# WQLT.net
KiCad netlist of a schematic drawn in Altium Designer
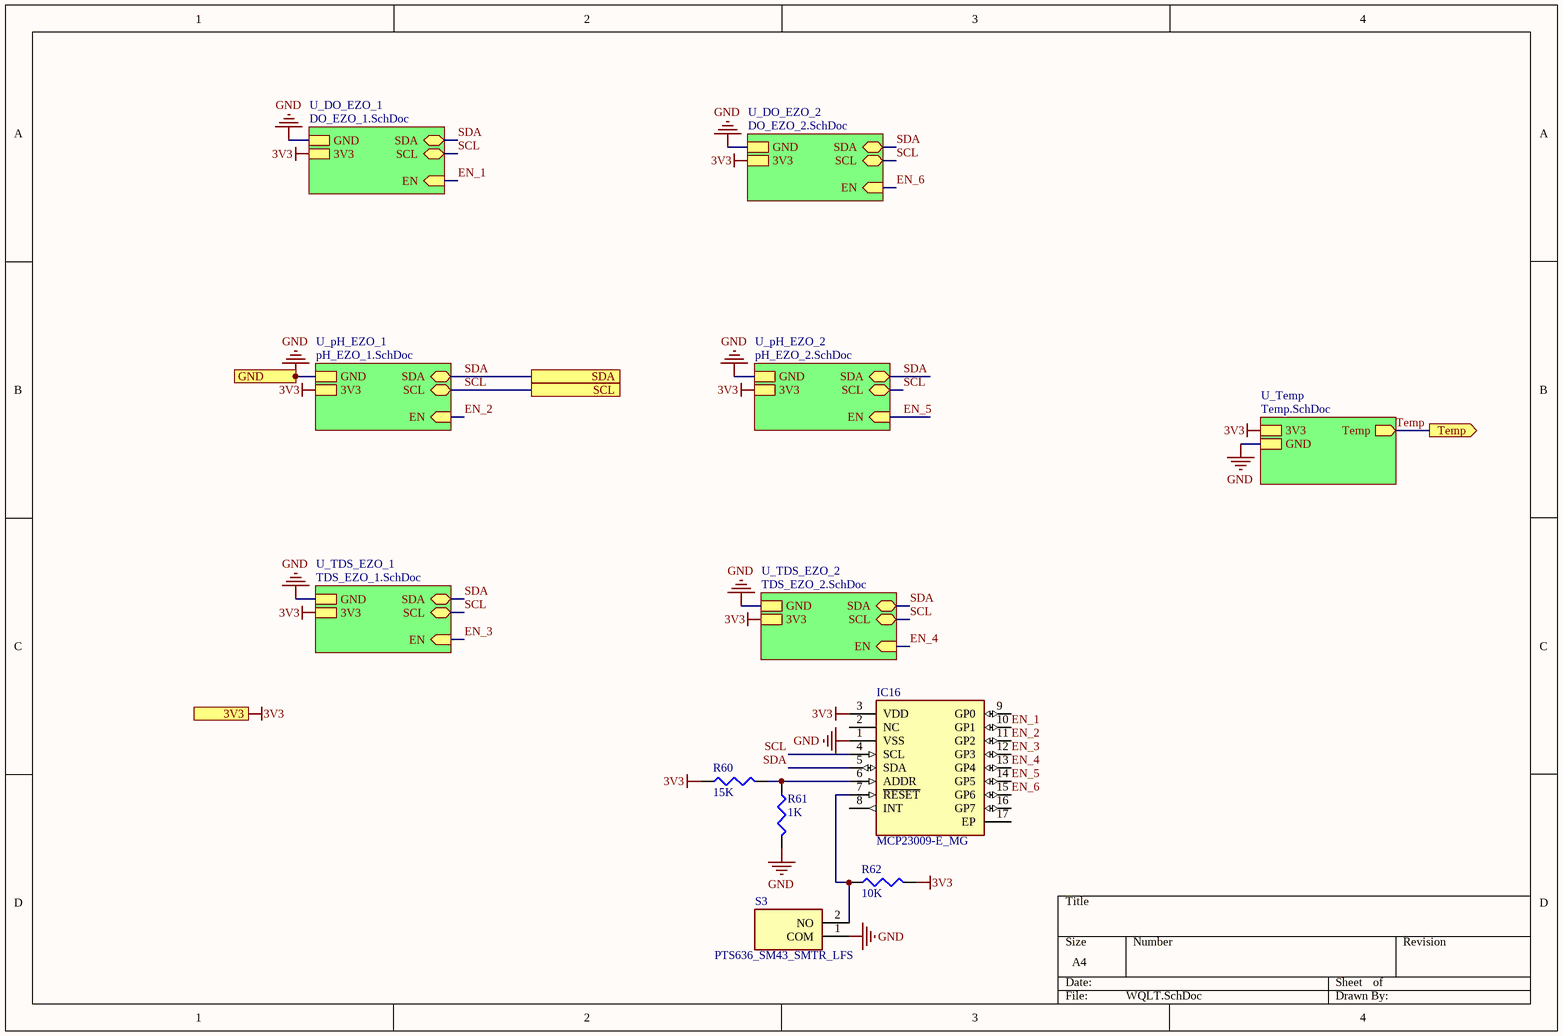
[diagram p0: WQLT.SchDoc]

(export (version "E")
  (design (tool "Eeschema 10.0.6"))
  (components
    (comp (ref "IC16")
      (value "MCP23009-E_MG")
      (footprint "SamacSys:QFN50P300X300X90-17N-D")
      (description "Integrated Circuit")
      (fields
        (field (name "MANUFACTURER_PART_NUMBER") "MCP23009-E/MG")
        (field (name "MOUSER PART NUMBER") "579-MCP23009-E/MG")
      )
      (libsource (lib "*") (part "MCP23009-E_MG"))
    )
    (comp (ref "R60")
      (value "15K")
      (footprint "J1-0603")
      (description "Resistor")
      (fields (field (name "PUBLISHER") "Altium Limited"))
      (libsource (lib "Miscellaneous Devices") (part "Res3"))
    )
    (comp (ref "R61")
      (value "1K")
      (footprint "J1-0603")
      (description "Resistor")
      (fields (field (name "PUBLISHER") "Altium Limited"))
      (libsource (lib "Miscellaneous Devices") (part "Res3"))
    )
    (comp (ref "R62")
      (value "10K")
      (footprint "J1-0603")
      (description "Resistor")
      (fields (field (name "PUBLISHER") "Altium Limited"))
      (libsource (lib "Miscellaneous Devices") (part "Res3"))
    )
    (comp (ref "S3")
      (value "PTS636_SM43_SMTR_LFS")
      (footprint "SamacSys:PTS636SM43SMTRLFS")
      (description "Switch")
      (fields
        (field (name "MANUFACTURER_PART_NUMBER") "PTS636 SM43 SMTR LFS")
        (field (name "MOUSER PART NUMBER") "611-PTS636SM43SMTRLF")
      )
      (libsource (lib "*") (part "PTS636_SM43_SMTR_LFS"))
    )
  )
  (nets
    (net (code "1") (name "/EN_1") (class "Default")
      (node (ref "IC16") (pin "10") (pinfunction "GP1_10") (pintype "bidirectional"))
    )
    (net (code "2") (name "/EN_2") (class "Default")
      (node (ref "IC16") (pin "11") (pinfunction "GP2_11") (pintype "bidirectional"))
    )
    (net (code "3") (name "/EN_3") (class "Default")
      (node (ref "IC16") (pin "12") (pinfunction "GP3_12") (pintype "bidirectional"))
    )
    (net (code "4") (name "/EN_4") (class "Default")
      (node (ref "IC16") (pin "13") (pinfunction "GP4_13") (pintype "bidirectional"))
    )
    (net (code "5") (name "/EN_5") (class "Default")
      (node (ref "IC16") (pin "14") (pinfunction "GP5_14") (pintype "bidirectional"))
    )
    (net (code "6") (name "/EN_6") (class "Default")
      (node (ref "IC16") (pin "15") (pinfunction "GP6_15") (pintype "bidirectional"))
    )
    (net (code "7") (name "/SCL") (class "Default")
      (node (ref "IC16") (pin "4") (pinfunction "SCL_4") (pintype "input"))
    )
    (net (code "8") (name "/SDA") (class "Default")
      (node (ref "IC16") (pin "5") (pinfunction "SDA_5") (pintype "bidirectional"))
    )
    (net (code "10") (name "3V3") (class "Default")
      (node (ref "IC16") (pin "3") (pinfunction "VDD_3") (pintype "power_in"))
      (node (ref "R60") (pin "1") (pinfunction "1_1") (pintype "passive"))
      (node (ref "R62") (pin "2") (pinfunction "2_2") (pintype "passive"))
    )
    (net (code "11") (name "GND") (class "Default")
      (node (ref "IC16") (pin "1") (pinfunction "VSS_1") (pintype "power_in"))
      (node (ref "R61") (pin "2") (pinfunction "2_2") (pintype "passive"))
      (node (ref "S3") (pin "1") (pinfunction "COM_1") (pintype "passive"))
    )
    (net (code "12") (name "Net-(IC16-ADDR)") (class "Default")
      (node (ref "IC16") (pin "6") (pinfunction "ADDR_6") (pintype "input"))
      (node (ref "R60") (pin "2") (pinfunction "2_2") (pintype "passive"))
      (node (ref "R61") (pin "1") (pinfunction "1_1") (pintype "passive"))
    )
    (net (code "13") (name "Net-(IC16-~{RESET})") (class "Default")
      (node (ref "IC16") (pin "7") (pinfunction "~{RESET}_7") (pintype "input"))
      (node (ref "R62") (pin "1") (pinfunction "1_1") (pintype "passive"))
      (node (ref "S3") (pin "2") (pinfunction "NO_2") (pintype "passive"))
    )
    (net (code "14") (name "unconnected-(IC16-EP-Pad17)") (class "Default")
      (node (ref "IC16") (pin "17") (pinfunction "EP_17") (pintype "passive"))
    )
    (net (code "15") (name "unconnected-(IC16-GP0-Pad9)") (class "Default")
      (node (ref "IC16") (pin "9") (pinfunction "GP0_9") (pintype "bidirectional"))
    )
    (net (code "16") (name "unconnected-(IC16-GP7-Pad16)") (class "Default")
      (node (ref "IC16") (pin "16") (pinfunction "GP7_16") (pintype "bidirectional"))
    )
    (net (code "17") (name "unconnected-(IC16-INT-Pad8)") (class "Default")
      (node (ref "IC16") (pin "8") (pinfunction "INT_8") (pintype "output"))
    )
    (net (code "18") (name "unconnected-(IC16-NC-Pad2)") (class "Default")
      (node (ref "IC16") (pin "2") (pinfunction "NC_2") (pintype "passive"))
    )
  )
)
